# MCU.net
KiCad netlist of a schematic drawn in Altium Designer
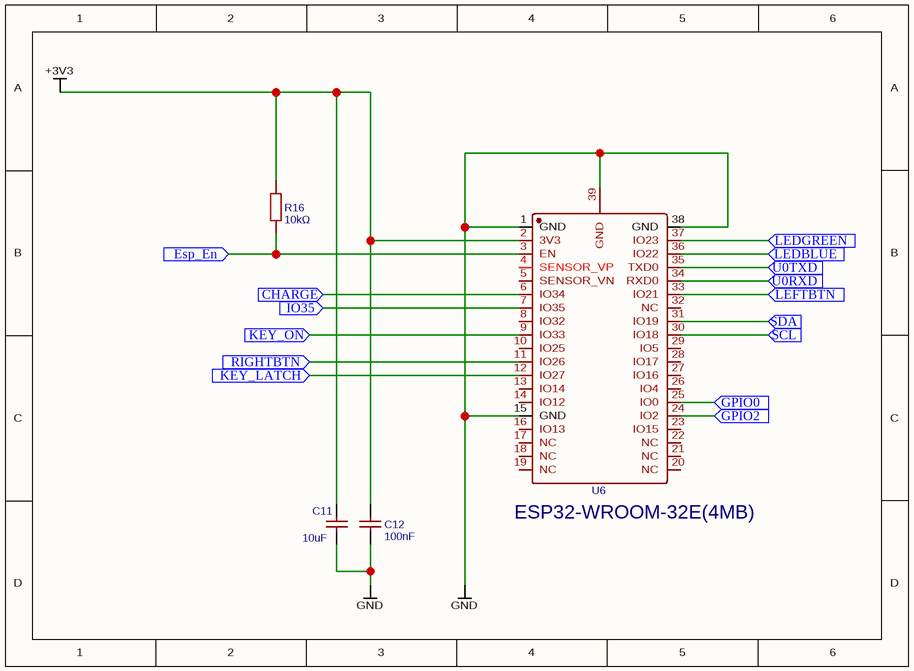
[diagram p0: MCU.schdoc]

(export (version "E")
  (design (tool "Eeschema 10.0.6"))
  (components
    (comp (ref "C11")
      (value "10uF")
      (fields
        (field (name "BOM_MANUFACTURER PART") "CL10A106MO8NQNC")
        (field (name "BOM_SUPPLIER PART") "C92487")
      )
      (libsource (lib "altium-import") (part "root_1_10uF_"))
    )
    (comp (ref "C12")
      (value "100nF")
      (fields
        (field (name "BOM_MANUFACTURER PART") "CL10B104KO8NNNC")
        (field (name "BOM_SUPPLIER PART") "C66501")
      )
      (libsource (lib "altium-import") (part "root_1_100nF_"))
    )
    (comp (ref "R16")
      (value "10kΩ")
      (fields
        (field (name "BOM_SUPPLIER PART") "C115324")
        (field (name "BOM_MANUFACTURER PART") "RS-03K1002FT")
        (field (name "CONTRIBUTOR") "LCSC")
      )
      (libsource (lib "altium-import") (part "root_1_10kΩ_"))
    )
    (comp (ref "U6")
      (value "ESP32-WROOM-32E(4MB)")
      (fields (field (name "BOM_SUPPLIER PART") "C701341") (field (name "CONTRIBUTOR") "LCSC"))
      (libsource (lib "altium-import") (part "root_0_ESP32-WROOM-32E(4MB)_"))
    )
  )
  (nets
    (net (code "1") (name "+3V3") (class "Default")
      (node (ref "C11") (pin "2") (pinfunction "2_2") (pintype "passive"))
      (node (ref "C12") (pin "2") (pinfunction "2_2") (pintype "passive"))
      (node (ref "R16") (pin "2") (pinfunction "2_2") (pintype "passive"))
      (node (ref "U6") (pin "2") (pinfunction "3V3_2") (pintype "passive"))
    )
    (net (code "2") (name "/CHARGE") (class "Default")
      (node (ref "U6") (pin "6") (pinfunction "IO34_6") (pintype "passive"))
    )
    (net (code "3") (name "/Esp_En") (class "Default")
      (node (ref "R16") (pin "1") (pinfunction "1_1") (pintype "passive"))
      (node (ref "U6") (pin "3") (pinfunction "EN_3") (pintype "passive"))
    )
    (net (code "4") (name "/GPIO0") (class "Default")
      (node (ref "U6") (pin "25") (pinfunction "IO0_25") (pintype "passive"))
    )
    (net (code "5") (name "/GPIO2") (class "Default")
      (node (ref "U6") (pin "24") (pinfunction "IO2_24") (pintype "passive"))
    )
    (net (code "6") (name "/IO35") (class "Default")
      (node (ref "U6") (pin "7") (pinfunction "IO35_7") (pintype "passive"))
    )
    (net (code "7") (name "/KEY_LATCH") (class "Default")
      (node (ref "U6") (pin "12") (pinfunction "IO27_12") (pintype "passive"))
    )
    (net (code "8") (name "/KEY_ON") (class "Default")
      (node (ref "U6") (pin "9") (pinfunction "IO33_9") (pintype "passive"))
    )
    (net (code "9") (name "/LEDBLUE") (class "Default")
      (node (ref "U6") (pin "36") (pinfunction "IO22_36") (pintype "passive"))
    )
    (net (code "10") (name "/LEDGREEN") (class "Default")
      (node (ref "U6") (pin "37") (pinfunction "IO23_37") (pintype "passive"))
    )
    (net (code "11") (name "/LEFTBTN") (class "Default")
      (node (ref "U6") (pin "33") (pinfunction "IO21_33") (pintype "passive"))
    )
    (net (code "12") (name "/RIGHTBTN") (class "Default")
      (node (ref "U6") (pin "11") (pinfunction "IO26_11") (pintype "passive"))
    )
    (net (code "13") (name "/SCL") (class "Default")
      (node (ref "U6") (pin "30") (pinfunction "IO18_30") (pintype "passive"))
    )
    (net (code "14") (name "/SDA") (class "Default")
      (node (ref "U6") (pin "31") (pinfunction "IO19_31") (pintype "passive"))
    )
    (net (code "15") (name "/U0RXD") (class "Default")
      (node (ref "U6") (pin "34") (pinfunction "RXD0_34") (pintype "passive"))
    )
    (net (code "16") (name "/U0TXD") (class "Default")
      (node (ref "U6") (pin "35") (pinfunction "TXD0_35") (pintype "passive"))
    )
    (net (code "17") (name "GND") (class "Default")
      (node (ref "C11") (pin "1") (pinfunction "1_1") (pintype "passive"))
      (node (ref "C12") (pin "1") (pinfunction "1_1") (pintype "passive"))
      (node (ref "U6") (pin "1") (pinfunction "GND_1") (pintype "passive"))
      (node (ref "U6") (pin "15") (pinfunction "GND_15") (pintype "passive"))
      (node (ref "U6") (pin "38") (pinfunction "GND_38") (pintype "passive"))
      (node (ref "U6") (pin "39") (pinfunction "GND_39") (pintype "passive"))
    )
    (net (code "18") (name "unconnected-(U6-IO4-Pad26)") (class "Default")
      (node (ref "U6") (pin "26") (pinfunction "IO4_26") (pintype "passive"))
    )
    (net (code "19") (name "unconnected-(U6-IO5-Pad29)") (class "Default")
      (node (ref "U6") (pin "29") (pinfunction "IO5_29") (pintype "passive"))
    )
    (net (code "20") (name "unconnected-(U6-IO12-Pad14)") (class "Default")
      (node (ref "U6") (pin "14") (pinfunction "IO12_14") (pintype "passive"))
    )
    (net (code "21") (name "unconnected-(U6-IO13-Pad16)") (class "Default")
      (node (ref "U6") (pin "16") (pinfunction "IO13_16") (pintype "passive"))
    )
    (net (code "22") (name "unconnected-(U6-IO14-Pad13)") (class "Default")
      (node (ref "U6") (pin "13") (pinfunction "IO14_13") (pintype "passive"))
    )
    (net (code "23") (name "unconnected-(U6-IO15-Pad23)") (class "Default")
      (node (ref "U6") (pin "23") (pinfunction "IO15_23") (pintype "passive"))
    )
    (net (code "24") (name "unconnected-(U6-IO16-Pad27)") (class "Default")
      (node (ref "U6") (pin "27") (pinfunction "IO16_27") (pintype "passive"))
    )
    (net (code "25") (name "unconnected-(U6-IO17-Pad28)") (class "Default")
      (node (ref "U6") (pin "28") (pinfunction "IO17_28") (pintype "passive"))
    )
    (net (code "26") (name "unconnected-(U6-IO25-Pad10)") (class "Default")
      (node (ref "U6") (pin "10") (pinfunction "IO25_10") (pintype "passive"))
    )
    (net (code "27") (name "unconnected-(U6-IO32-Pad8)") (class "Default")
      (node (ref "U6") (pin "8") (pinfunction "IO32_8") (pintype "passive"))
    )
    (net (code "28") (name "unconnected-(U6-NC-Pad17)") (class "Default")
      (node (ref "U6") (pin "17") (pinfunction "NC_17") (pintype "passive"))
    )
    (net (code "29") (name "unconnected-(U6-NC-Pad18)") (class "Default")
      (node (ref "U6") (pin "18") (pinfunction "NC_18") (pintype "passive"))
    )
    (net (code "30") (name "unconnected-(U6-NC-Pad19)") (class "Default")
      (node (ref "U6") (pin "19") (pinfunction "NC_19") (pintype "passive"))
    )
    (net (code "31") (name "unconnected-(U6-NC-Pad20)") (class "Default")
      (node (ref "U6") (pin "20") (pinfunction "NC_20") (pintype "passive"))
    )
    (net (code "32") (name "unconnected-(U6-NC-Pad21)") (class "Default")
      (node (ref "U6") (pin "21") (pinfunction "NC_21") (pintype "passive"))
    )
    (net (code "33") (name "unconnected-(U6-NC-Pad22)") (class "Default")
      (node (ref "U6") (pin "22") (pinfunction "NC_22") (pintype "passive"))
    )
    (net (code "34") (name "unconnected-(U6-NC-Pad32)") (class "Default")
      (node (ref "U6") (pin "32") (pinfunction "NC_32") (pintype "passive"))
    )
    (net (code "35") (name "unconnected-(U6-SENSOR_VN-Pad5)") (class "Default")
      (node (ref "U6") (pin "5") (pinfunction "SENSOR_VN_5") (pintype "passive"))
    )
    (net (code "36") (name "unconnected-(U6-SENSOR_VP-Pad4)") (class "Default")
      (node (ref "U6") (pin "4") (pinfunction "SENSOR_VP_4") (pintype "passive"))
    )
  )
)
